# 6coils-1-discrete.net
KiCad netlist of a schematic drawn in EasyEDA
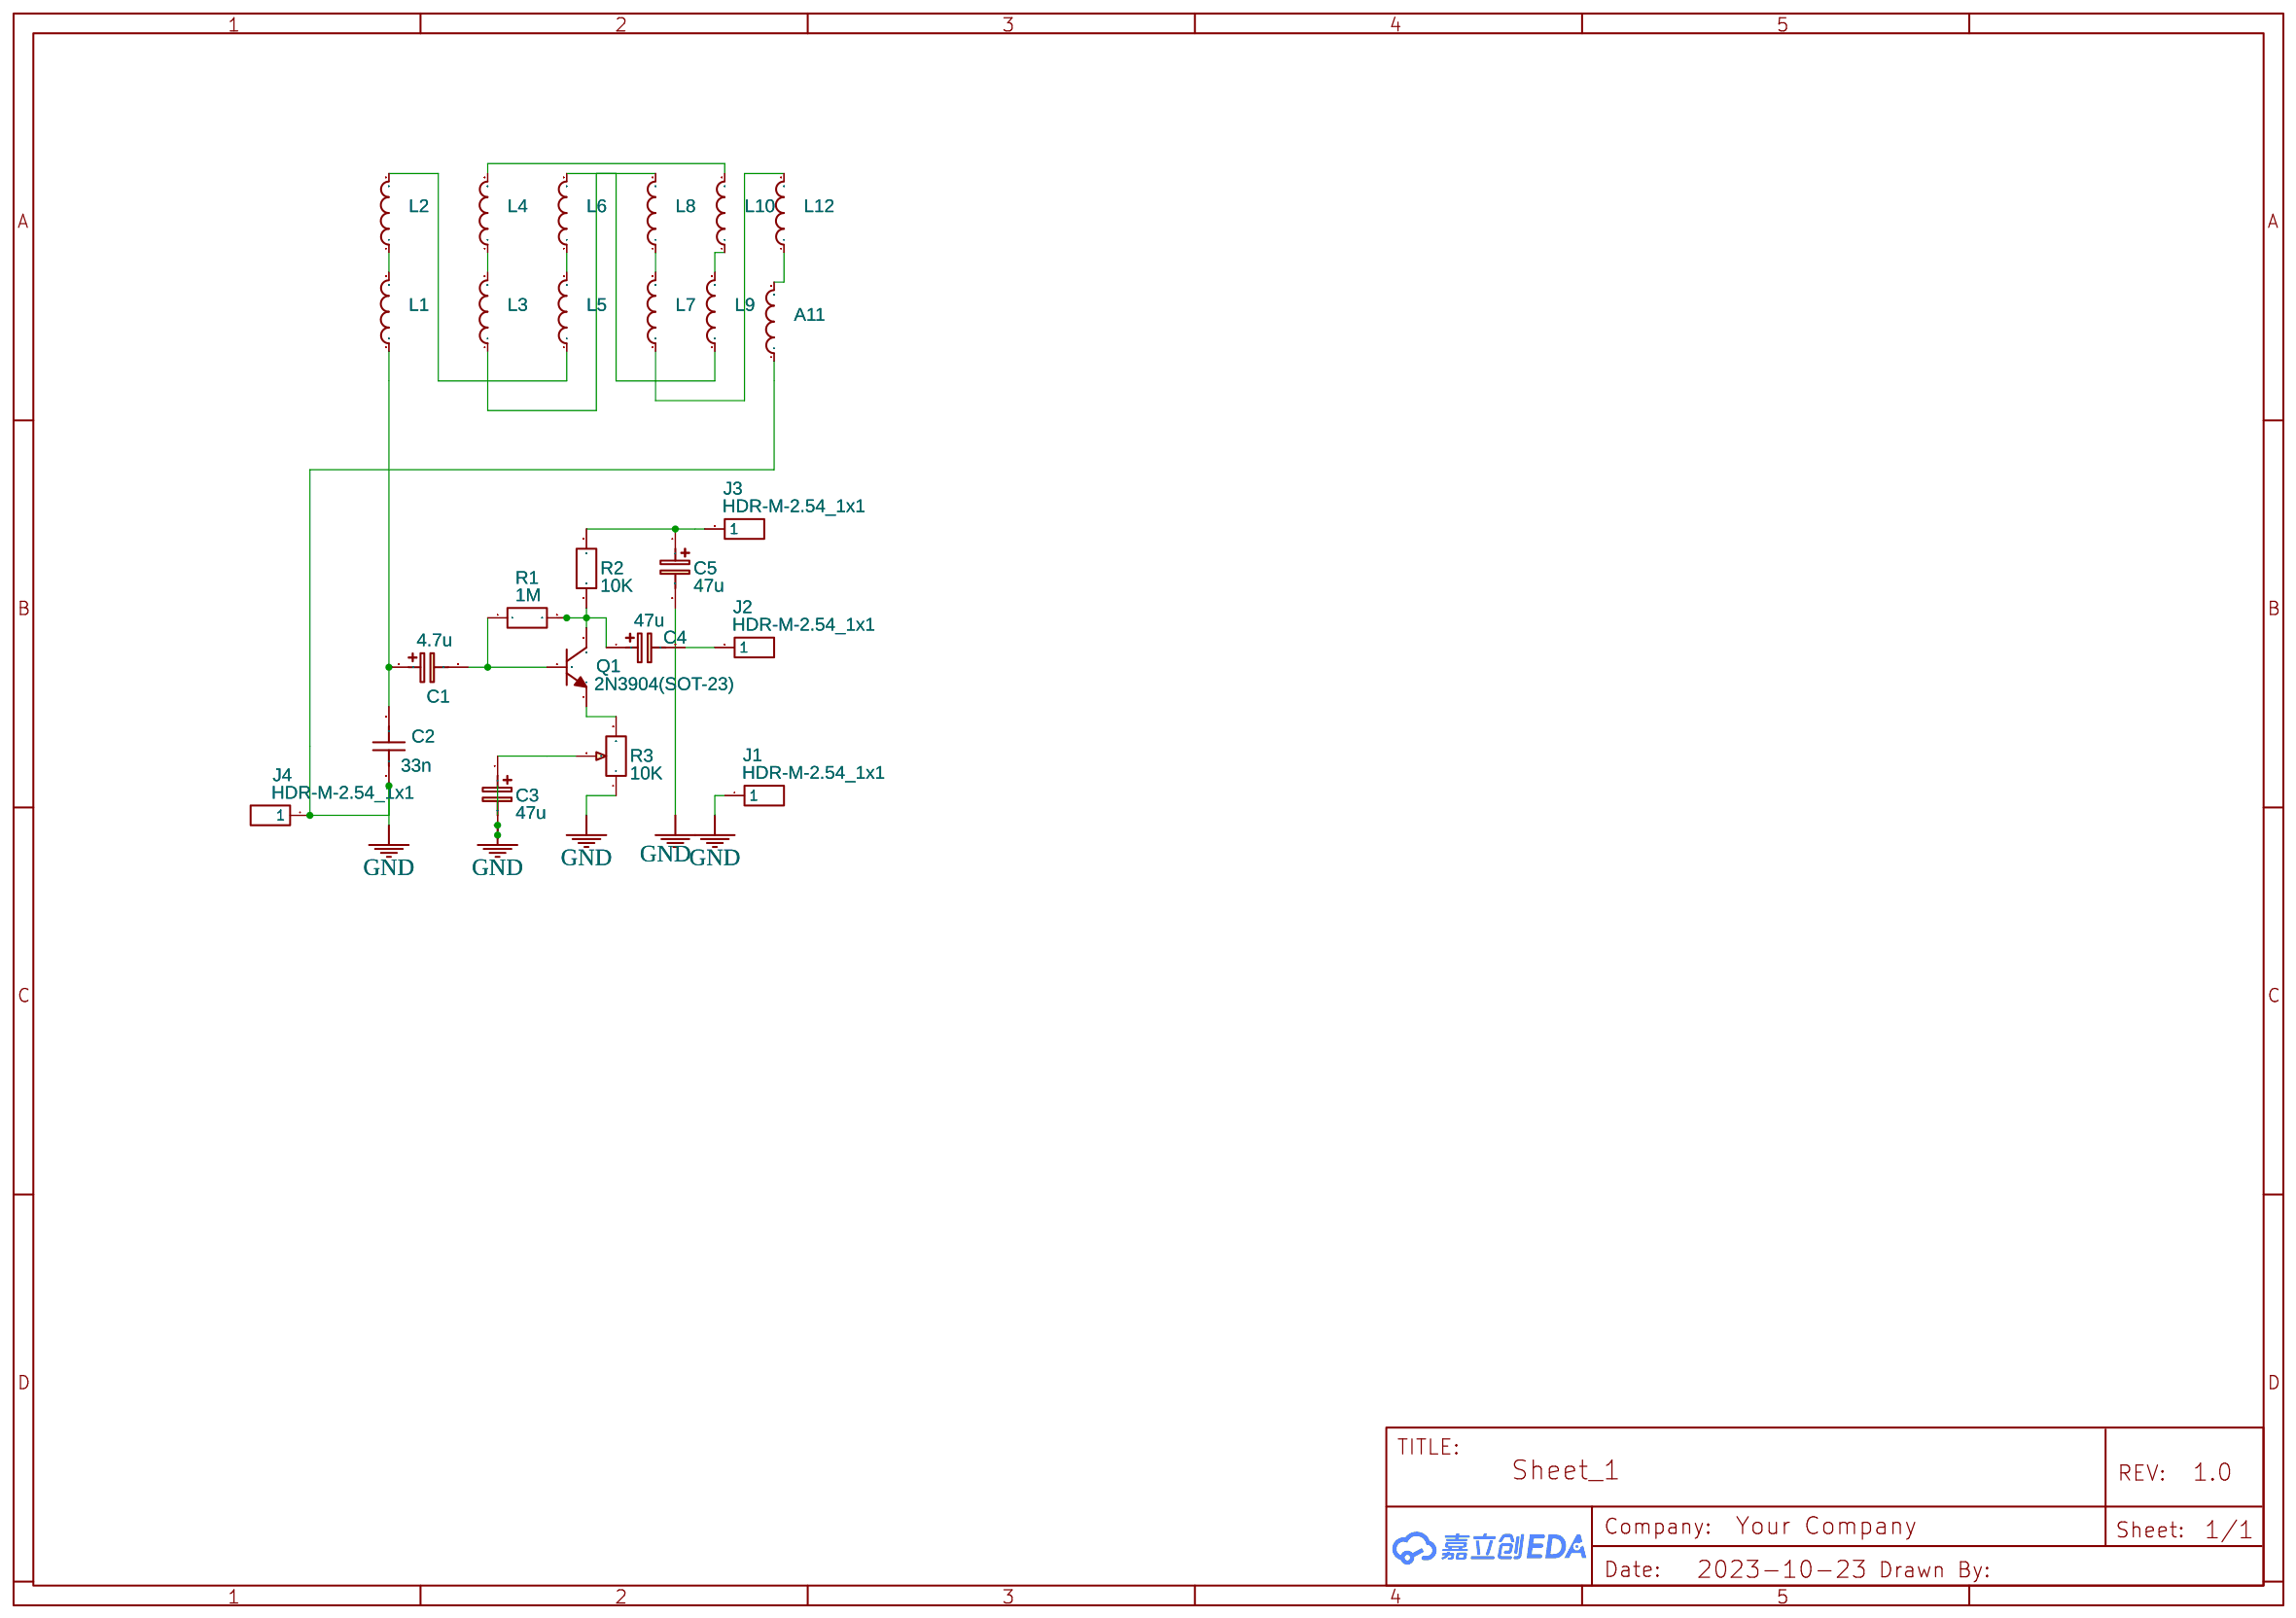
[diagram p0: schematic sheet]

(export (version "E")
  (design (tool "Eeschema 10.0.6"))
  (components
    (comp (ref "A11")
      (value "INDUCTOR_SMD:L_COILCRAFT_XXL4040")
      (fields (field (name "Manufacturer Part") "Inductor_SMD:L_Coilcraft_XxL4040"))
      (libsource (lib "") (part "INDUCTOR_SMD{colon}L_COILCRAFT_XXL4040_2"))
    )
    (comp (ref "C1") (value "4.7u") (libsource (lib "") (part "C_Tan_SMD_A_EU")))
    (comp (ref "C2") (value "33n") (libsource (lib "") (part "C_0603_US")))
    (comp (ref "C3") (value "47u") (libsource (lib "") (part "C_Tan_SMD_A_EU_1")))
    (comp (ref "C4") (value "47u") (libsource (lib "") (part "C_Tan_SMD_A_EU_3")))
    (comp (ref "C5") (value "47u") (libsource (lib "") (part "C_Tan_SMD_A_EU_2")))
    (comp (ref "J1")
      (value "HDR-M-2.54_1x1")
      (fields (field (name "BOM_Supplier Part") "C81276"))
      (libsource (lib "") (part "HDR-M-2.54_1x1"))
    )
    (comp (ref "J2")
      (value "HDR-M-2.54_1x1")
      (fields (field (name "BOM_Supplier Part") "C81276"))
      (libsource (lib "") (part "HDR-M-2.54_1x1"))
    )
    (comp (ref "J3")
      (value "HDR-M-2.54_1x1")
      (fields (field (name "BOM_Supplier Part") "C81276"))
      (libsource (lib "") (part "HDR-M-2.54_1x1"))
    )
    (comp (ref "J4")
      (value "HDR-M-2.54_1x1")
      (fields (field (name "BOM_Supplier Part") "C81276"))
      (libsource (lib "") (part "HDR-M-2.54_1x1_1"))
    )
    (comp (ref "L1")
      (value "INDUCTOR_SMD:L_COILCRAFT_XXL4040")
      (fields (field (name "Manufacturer Part") "Inductor_SMD:L_Coilcraft_XxL4040"))
      (libsource (lib "") (part "INDUCTOR_SMD{colon}L_COILCRAFT_XXL4040"))
    )
    (comp (ref "L2")
      (value "INDUCTOR_SMD:L_COILCRAFT_XXL4040")
      (fields (field (name "Manufacturer Part") "Inductor_SMD:L_Coilcraft_XxL4040"))
      (libsource (lib "") (part "INDUCTOR_SMD{colon}L_COILCRAFT_XXL4040"))
    )
    (comp (ref "L3")
      (value "INDUCTOR_SMD:L_COILCRAFT_XXL4040")
      (fields (field (name "Manufacturer Part") "Inductor_SMD:L_Coilcraft_XxL4040"))
      (libsource (lib "") (part "INDUCTOR_SMD{colon}L_COILCRAFT_XXL4040"))
    )
    (comp (ref "L4")
      (value "INDUCTOR_SMD:L_COILCRAFT_XXL4040")
      (fields (field (name "Manufacturer Part") "Inductor_SMD:L_Coilcraft_XxL4040"))
      (libsource (lib "") (part "INDUCTOR_SMD{colon}L_COILCRAFT_XXL4040"))
    )
    (comp (ref "L5")
      (value "INDUCTOR_SMD:L_COILCRAFT_XXL4040")
      (fields (field (name "Manufacturer Part") "Inductor_SMD:L_Coilcraft_XxL4040"))
      (libsource (lib "") (part "INDUCTOR_SMD{colon}L_COILCRAFT_XXL4040_1"))
    )
    (comp (ref "L6")
      (value "INDUCTOR_SMD:L_COILCRAFT_XXL4040")
      (fields (field (name "Manufacturer Part") "Inductor_SMD:L_Coilcraft_XxL4040"))
      (libsource (lib "") (part "INDUCTOR_SMD{colon}L_COILCRAFT_XXL4040_1"))
    )
    (comp (ref "L7")
      (value "INDUCTOR_SMD:L_COILCRAFT_XXL4040")
      (fields (field (name "Manufacturer Part") "Inductor_SMD:L_Coilcraft_XxL4040"))
      (libsource (lib "") (part "INDUCTOR_SMD{colon}L_COILCRAFT_XXL4040_1"))
    )
    (comp (ref "L8")
      (value "INDUCTOR_SMD:L_COILCRAFT_XXL4040")
      (fields (field (name "Manufacturer Part") "Inductor_SMD:L_Coilcraft_XxL4040"))
      (libsource (lib "") (part "INDUCTOR_SMD{colon}L_COILCRAFT_XXL4040_1"))
    )
    (comp (ref "L9")
      (value "INDUCTOR_SMD:L_COILCRAFT_XXL4040")
      (fields (field (name "Manufacturer Part") "Inductor_SMD:L_Coilcraft_XxL4040"))
      (libsource (lib "") (part "INDUCTOR_SMD{colon}L_COILCRAFT_XXL4040_1"))
    )
    (comp (ref "L10")
      (value "INDUCTOR_SMD:L_COILCRAFT_XXL4040")
      (fields (field (name "Manufacturer Part") "Inductor_SMD:L_Coilcraft_XxL4040"))
      (libsource (lib "") (part "INDUCTOR_SMD{colon}L_COILCRAFT_XXL4040_1"))
    )
    (comp (ref "L12")
      (value "INDUCTOR_SMD:L_COILCRAFT_XXL4040")
      (fields (field (name "Manufacturer Part") "Inductor_SMD:L_Coilcraft_XxL4040"))
      (libsource (lib "") (part "INDUCTOR_SMD{colon}L_COILCRAFT_XXL4040_1"))
    )
    (comp (ref "Q1")
      (value "2N3904(SOT-23)")
      (fields
        (field (name "BOM_Manufacturer Part") "2n3904S-RTK/PS")
        (field (name "BOM_Supplier Part") "C18536")
      )
      (libsource (lib "") (part "2N3904(SOT-23)"))
    )
    (comp (ref "R1") (value "1M") (libsource (lib "") (part "R_0603_EU_1")))
    (comp (ref "R2") (value "10K") (libsource (lib "") (part "R_0603_EU")))
    (comp (ref "R3")
      (value "10K")
      (fields (field (name "Manufacturer Part") "RM063-103 10K") (field (name "Manufacturer") "JML"))
      (libsource (lib "") (part "RM063-103 10K"))
    )
  )
  (nets
    (net (code "1") (name "GND") (class "Default")
      (node (ref "A11") (pin "1") (pinfunction "1_1") (pintype "unspecified"))
      (node (ref "C2") (pin "1") (pinfunction "1_1") (pintype "unspecified"))
      (node (ref "C3") (pin "2") (pinfunction "2_2") (pintype "unspecified"))
      (node (ref "C5") (pin "2") (pinfunction "2_2") (pintype "unspecified"))
      (node (ref "J1") (pin "1") (pinfunction "1_1") (pintype "input"))
      (node (ref "J4") (pin "1") (pinfunction "1_1") (pintype "input"))
      (node (ref "R3") (pin "1") (pinfunction "1_1") (pintype "input"))
    )
    (net (code "2") (name "Net-(A11-Pad2)") (class "Default")
      (node (ref "A11") (pin "2") (pinfunction "2_2") (pintype "unspecified"))
      (node (ref "L12") (pin "1") (pinfunction "1_1") (pintype "unspecified"))
    )
    (net (code "3") (name "Net-(C1-Pad1)") (class "Default")
      (node (ref "C1") (pin "1") (pinfunction "1_1") (pintype "unspecified"))
      (node (ref "C2") (pin "2") (pinfunction "2_2") (pintype "unspecified"))
      (node (ref "L1") (pin "1") (pinfunction "1_1") (pintype "unspecified"))
    )
    (net (code "4") (name "Net-(C3-Pad1)") (class "Default")
      (node (ref "C3") (pin "1") (pinfunction "1_1") (pintype "unspecified"))
      (node (ref "R3") (pin "2") (pinfunction "2_2") (pintype "input"))
    )
    (net (code "5") (name "Net-(C4-Pad2)") (class "Default")
      (node (ref "C4") (pin "2") (pinfunction "2_2") (pintype "unspecified"))
      (node (ref "J2") (pin "1") (pinfunction "1_1") (pintype "input"))
    )
    (net (code "6") (name "Net-(C5-Pad1)") (class "Default")
      (node (ref "C5") (pin "1") (pinfunction "1_1") (pintype "unspecified"))
      (node (ref "J3") (pin "1") (pinfunction "1_1") (pintype "input"))
      (node (ref "R2") (pin "2") (pinfunction "2_2") (pintype "unspecified"))
    )
    (net (code "7") (name "Net-(L1-Pad2)") (class "Default")
      (node (ref "L1") (pin "2") (pinfunction "2_2") (pintype "unspecified"))
      (node (ref "L2") (pin "1") (pinfunction "1_1") (pintype "unspecified"))
    )
    (net (code "8") (name "Net-(L2-Pad2)") (class "Default")
      (node (ref "L2") (pin "2") (pinfunction "2_2") (pintype "unspecified"))
      (node (ref "L5") (pin "1") (pinfunction "1_1") (pintype "unspecified"))
    )
    (net (code "9") (name "Net-(L3-Pad1)") (class "Default")
      (node (ref "L3") (pin "1") (pinfunction "1_1") (pintype "unspecified"))
      (node (ref "L8") (pin "2") (pinfunction "2_2") (pintype "unspecified"))
    )
    (net (code "10") (name "Net-(L3-Pad2)") (class "Default")
      (node (ref "L3") (pin "2") (pinfunction "2_2") (pintype "unspecified"))
      (node (ref "L4") (pin "1") (pinfunction "1_1") (pintype "unspecified"))
    )
    (net (code "11") (name "Net-(L5-Pad2)") (class "Default")
      (node (ref "L5") (pin "2") (pinfunction "2_2") (pintype "unspecified"))
      (node (ref "L6") (pin "1") (pinfunction "1_1") (pintype "unspecified"))
    )
    (net (code "12") (name "Net-(L6-Pad2)") (class "Default")
      (node (ref "L6") (pin "2") (pinfunction "2_2") (pintype "unspecified"))
      (node (ref "L9") (pin "1") (pinfunction "1_1") (pintype "unspecified"))
    )
    (net (code "13") (name "Net-(L7-Pad2)") (class "Default")
      (node (ref "L7") (pin "2") (pinfunction "2_2") (pintype "unspecified"))
      (node (ref "L8") (pin "1") (pinfunction "1_1") (pintype "unspecified"))
    )
    (net (code "14") (name "Net-(L10-Pad1)") (class "Default")
      (node (ref "L10") (pin "1") (pinfunction "1_1") (pintype "unspecified"))
      (node (ref "L9") (pin "2") (pinfunction "2_2") (pintype "unspecified"))
    )
    (net (code "15") (name "Net-(L10-Pad2)") (class "Default")
      (node (ref "L10") (pin "2") (pinfunction "2_2") (pintype "unspecified"))
      (node (ref "L4") (pin "2") (pinfunction "2_2") (pintype "unspecified"))
    )
    (net (code "16") (name "Net-(L12-Pad2)") (class "Default")
      (node (ref "L12") (pin "2") (pinfunction "2_2") (pintype "unspecified"))
      (node (ref "L7") (pin "1") (pinfunction "1_1") (pintype "unspecified"))
    )
    (net (code "17") (name "Net-(Q1-B)") (class "Default")
      (node (ref "C1") (pin "2") (pinfunction "2_2") (pintype "unspecified"))
      (node (ref "Q1") (pin "2") (pinfunction "B_2") (pintype "input"))
      (node (ref "R1") (pin "1") (pinfunction "1_1") (pintype "unspecified"))
    )
    (net (code "18") (name "Net-(Q1-C)") (class "Default")
      (node (ref "C4") (pin "1") (pinfunction "1_1") (pintype "unspecified"))
      (node (ref "Q1") (pin "3") (pinfunction "C_3") (pintype "input"))
      (node (ref "R1") (pin "2") (pinfunction "2_2") (pintype "unspecified"))
      (node (ref "R2") (pin "1") (pinfunction "1_1") (pintype "unspecified"))
    )
    (net (code "19") (name "Net-(Q1-E)") (class "Default")
      (node (ref "Q1") (pin "1") (pinfunction "E_1") (pintype "input"))
      (node (ref "R3") (pin "3") (pinfunction "3_3") (pintype "input"))
    )
  )
)
